# SolderingStation_Control_-_Using_Mux_for.net
KiCad netlist of a schematic drawn in Altium Designer
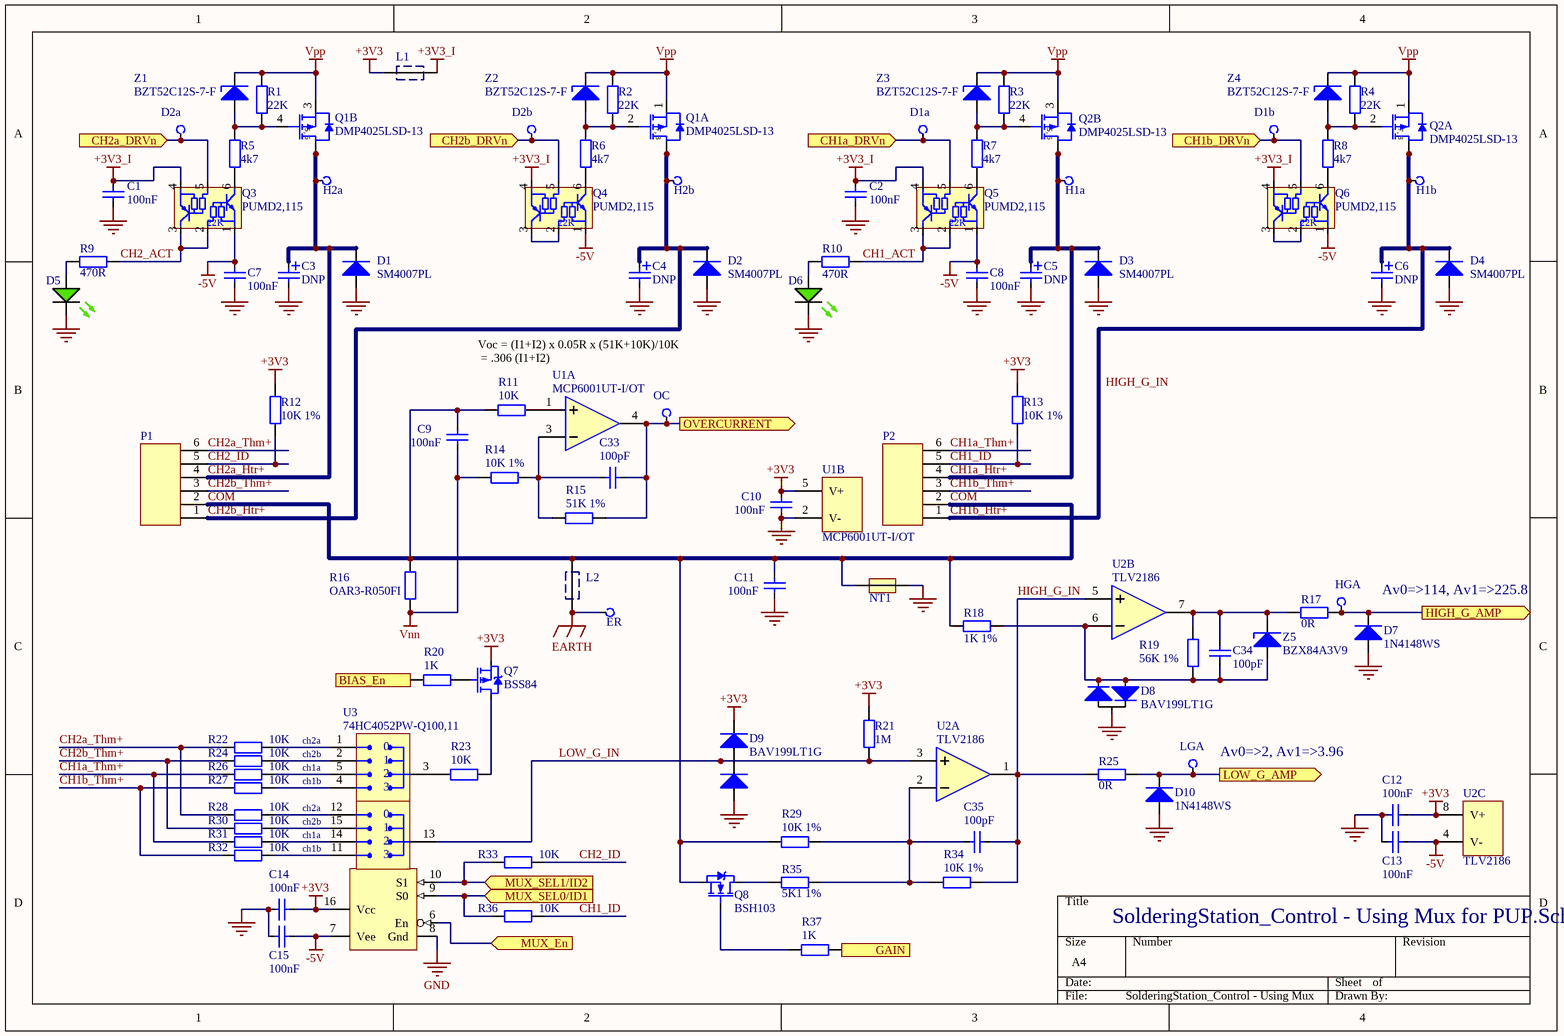
[diagram p0: SolderingStation_Control - Using Mux for PUP.SchDoc]

(export (version "E")
  (design (tool "Eeschema 10.0.6"))
  (components
    (comp (ref "C1")
      (value "100nF")
      (footprint "CCNP1608-0603")
      (description "Capacitor non-polar SMT 0603")
      (fields
        (field (name "MANUFACTURER") "Generic Components")
        (field (name "PUBLISHER") "Altium Hobart Technology Centre")
      )
      (libsource (lib "MyLibrary") (part "Cap_CCNP_0603"))
    )
    (comp (ref "C2")
      (value "100nF")
      (footprint "CCNP1608-0603")
      (description "Capacitor non-polar SMT 0603")
      (fields
        (field (name "MANUFACTURER") "Generic Components")
        (field (name "PUBLISHER") "Altium Hobart Technology Centre")
      )
      (libsource (lib "MyLibrary") (part "Cap_CCNP_0603"))
    )
    (comp (ref "C3")
      (value "DNP")
      (footprint "CC2012-0805")
      (description "Capacitor SMT 0805")
      (fields
        (field (name "MANUFACTURER") "Generic Components")
        (field (name "PUBLISHER") "Altium Hobart Technology Centre")
      )
      (libsource (lib "MyLibrary") (part "Cap_CC_0805"))
    )
    (comp (ref "C4")
      (value "DNP")
      (footprint "CC2012-0805")
      (description "Capacitor SMT 0805")
      (fields
        (field (name "MANUFACTURER") "Generic Components")
        (field (name "PUBLISHER") "Altium Hobart Technology Centre")
      )
      (libsource (lib "MyLibrary") (part "Cap_CC_0805"))
    )
    (comp (ref "C5")
      (value "DNP")
      (footprint "CC2012-0805")
      (description "Capacitor SMT 0805")
      (fields
        (field (name "MANUFACTURER") "Generic Components")
        (field (name "PUBLISHER") "Altium Hobart Technology Centre")
      )
      (libsource (lib "MyLibrary") (part "Cap_CC_0805"))
    )
    (comp (ref "C6")
      (value "DNP")
      (footprint "CC2012-0805")
      (description "Capacitor SMT 0805")
      (fields
        (field (name "MANUFACTURER") "Generic Components")
        (field (name "PUBLISHER") "Altium Hobart Technology Centre")
      )
      (libsource (lib "MyLibrary") (part "Cap_CC_0805"))
    )
    (comp (ref "C7")
      (value "100nF")
      (footprint "CCNP1608-0603")
      (description "Capacitor non-polar SMT 0603")
      (fields
        (field (name "MANUFACTURER") "Generic Components")
        (field (name "PUBLISHER") "Altium Hobart Technology Centre")
      )
      (libsource (lib "MyLibrary") (part "Cap_CCNP_0603"))
    )
    (comp (ref "C8")
      (value "100nF")
      (footprint "CCNP1608-0603")
      (description "Capacitor non-polar SMT 0603")
      (fields
        (field (name "MANUFACTURER") "Generic Components")
        (field (name "PUBLISHER") "Altium Hobart Technology Centre")
      )
      (libsource (lib "MyLibrary") (part "Cap_CCNP_0603"))
    )
    (comp (ref "C9")
      (value "100nF")
      (footprint "CCNP1608-0603")
      (description "Capacitor non-polar SMT 0603")
      (fields
        (field (name "MANUFACTURER") "Generic Components")
        (field (name "PUBLISHER") "Altium Hobart Technology Centre")
      )
      (libsource (lib "MyLibrary") (part "Cap_CCNP_0603"))
    )
    (comp (ref "C10")
      (value "100nF")
      (footprint "CCNP1608-0603")
      (description "Capacitor non-polar SMT 0603")
      (fields
        (field (name "MANUFACTURER") "Generic Components")
        (field (name "PUBLISHER") "Altium Hobart Technology Centre")
      )
      (libsource (lib "MyLibrary") (part "Cap_CCNP_0603"))
    )
    (comp (ref "C11")
      (value "100nF")
      (footprint "CCNP1608-0603")
      (description "Capacitor non-polar SMT 0603")
      (fields
        (field (name "MANUFACTURER") "Generic Components")
        (field (name "PUBLISHER") "Altium Hobart Technology Centre")
      )
      (libsource (lib "MyLibrary") (part "Cap_CCNP_0603"))
    )
    (comp (ref "C12")
      (value "100nF")
      (footprint "CCNP1608-0603")
      (description "Capacitor non-polar SMT 0603")
      (fields
        (field (name "MANUFACTURER") "Generic Components")
        (field (name "PUBLISHER") "Altium Hobart Technology Centre")
      )
      (libsource (lib "MyLibrary") (part "Cap_CCNP_0603"))
    )
    (comp (ref "C13")
      (value "100nF")
      (footprint "CCNP1608-0603")
      (description "Capacitor non-polar SMT 0603")
      (fields
        (field (name "MANUFACTURER") "Generic Components")
        (field (name "PUBLISHER") "Altium Hobart Technology Centre")
      )
      (libsource (lib "MyLibrary") (part "Cap_CCNP_0603"))
    )
    (comp (ref "C14")
      (value "100nF")
      (footprint "CCNP1608-0603")
      (description "Capacitor non-polar SMT 0603")
      (fields
        (field (name "MANUFACTURER") "Generic Components")
        (field (name "PUBLISHER") "Altium Hobart Technology Centre")
      )
      (libsource (lib "MyLibrary") (part "Cap_CCNP_0603"))
    )
    (comp (ref "C15")
      (value "100nF")
      (footprint "CCNP1608-0603")
      (description "Capacitor non-polar SMT 0603")
      (fields
        (field (name "MANUFACTURER") "Generic Components")
        (field (name "PUBLISHER") "Altium Hobart Technology Centre")
      )
      (libsource (lib "MyLibrary") (part "Cap_CCNP_0603"))
    )
    (comp (ref "C33")
      (value "100pF")
      (footprint "CCNP1608-0603")
      (description "Capacitor non-polar SMT 0603")
      (fields
        (field (name "MANUFACTURER") "Generic Components")
        (field (name "PUBLISHER") "Altium Hobart Technology Centre")
      )
      (libsource (lib "MyLibrary") (part "Cap_CCNP_0603"))
    )
    (comp (ref "C34")
      (value "100pF")
      (footprint "CCNP1608-0603")
      (description "Capacitor non-polar SMT 0603")
      (fields
        (field (name "MANUFACTURER") "Generic Components")
        (field (name "PUBLISHER") "Altium Hobart Technology Centre")
      )
      (libsource (lib "MyLibrary") (part "Cap_CCNP_0603"))
    )
    (comp (ref "C35")
      (value "100pF")
      (footprint "CCNP1608-0603")
      (description "Capacitor non-polar SMT 0603")
      (fields
        (field (name "MANUFACTURER") "Generic Components")
        (field (name "PUBLISHER") "Altium Hobart Technology Centre")
      )
      (libsource (lib "MyLibrary") (part "Cap_CCNP_0603"))
    )
    (comp (ref "D1")
      (value "SM4007PL")
      (footprint "SOD-123FL")
      (description "Diodes - General Purpose, 1kV 1A 1.1V 1A SOD-123FL")
      (libsource (lib "MyLibrary") (part "SM4007PL"))
    )
    (comp (ref "D1a")
      (value "Drive1")
      (footprint "PCBPIN - 0.7mm")
      (description "Test Point")
      (libsource (lib "MyLibrary") (part "TP"))
    )
    (comp (ref "D1b")
      (value "Drive2")
      (footprint "PCBPIN - 0.7mm")
      (description "Test Point")
      (libsource (lib "MyLibrary") (part "TP"))
    )
    (comp (ref "D2")
      (value "SM4007PL")
      (footprint "SOD-123FL")
      (description "Diodes - General Purpose, 1kV 1A 1.1V 1A SOD-123FL")
      (libsource (lib "MyLibrary") (part "SM4007PL"))
    )
    (comp (ref "D2a")
      (value "Drive2")
      (footprint "PCBPIN - 0.7mm")
      (description "Test Point")
      (libsource (lib "MyLibrary") (part "TP"))
    )
    (comp (ref "D2b")
      (value "Drive2")
      (footprint "PCBPIN - 0.7mm")
      (description "Test Point")
      (libsource (lib "MyLibrary") (part "TP"))
    )
    (comp (ref "D3")
      (value "SM4007PL")
      (footprint "SOD-123FL")
      (description "Diodes - General Purpose, 1kV 1A 1.1V 1A SOD-123FL")
      (libsource (lib "MyLibrary") (part "SM4007PL"))
    )
    (comp (ref "D4")
      (value "SM4007PL")
      (footprint "SOD-123FL")
      (description "Diodes - General Purpose, 1kV 1A 1.1V 1A SOD-123FL")
      (libsource (lib "MyLibrary") (part "SM4007PL"))
    )
    (comp (ref "D5")
      (value "LED")
      (footprint "LED3MM-GREEN - 10mm Proud")
      (description "3mm Green LED")
      (fields (field (name "MANUFACTURER") "Generic Components") (field (name "PUBLISHER") "Altium Limited"))
      (libsource (lib "MySchLib") (part "LED_3MM_GREEN"))
    )
    (comp (ref "D6")
      (value "LED")
      (footprint "LED3MM-GREEN - 10mm Proud")
      (description "3mm Green LED")
      (fields (field (name "MANUFACTURER") "Generic Components") (field (name "PUBLISHER") "Altium Limited"))
      (libsource (lib "MySchLib") (part "LED_3MM_GREEN"))
    )
    (comp (ref "D7")
      (value "1N4148WS")
      (footprint "SOD-323")
      (description "Switching Diode 100V 150mA 1.25V@150mA 4ns SOD-323")
      (libsource (lib "MyLibrary") (part "1N4148WS"))
    )
    (comp (ref "D8")
      (value "BAV199LT1G")
      (footprint "SOT23_M")
      (description "Dual Series low-leakage switching diodes, 3-Pin SOT-23")
      (libsource (lib "MyLibrary") (part "BAV199LT1G"))
    )
    (comp (ref "D9")
      (value "BAV199LT1G")
      (footprint "SOT23_M")
      (description "Dual Series low-leakage switching diodes, 3-Pin SOT-23")
      (libsource (lib "MySchLib") (part "BAV199LT1G"))
    )
    (comp (ref "D10")
      (value "1N4148WS")
      (footprint "SOD-323")
      (description "Switching Diode 100V 150mA 1.25V@150mA 4ns SOD-323")
      (libsource (lib "MyLibrary") (part "1N4148WS"))
    )
    (comp (ref "ER")
      (value "Gnd")
      (footprint "PCBPIN - 1mm")
      (description "Test Point")
      (libsource (lib "") (part "TP_1"))
    )
    (comp (ref "H1a")
      (value "Heater1")
      (footprint "PCBPIN - 0.7mm")
      (description "Test Point")
      (libsource (lib "") (part "TP_1"))
    )
    (comp (ref "H1b")
      (value "Heater2")
      (footprint "PCBPIN - 0.7mm")
      (description "Test Point")
      (libsource (lib "") (part "TP_1"))
    )
    (comp (ref "H2a")
      (value "Heater2")
      (footprint "PCBPIN - 0.7mm")
      (description "Test Point")
      (libsource (lib "") (part "TP_1"))
    )
    (comp (ref "H2b")
      (value "Heater2")
      (footprint "PCBPIN - 0.7mm")
      (description "Test Point")
      (libsource (lib "") (part "TP_1"))
    )
    (comp (ref "HGA")
      (value "TC1")
      (footprint "PCBPIN - 0.7mm")
      (description "Test Point")
      (libsource (lib "MyLibrary") (part "TP"))
    )
    (comp (ref "L1")
      (value "Ferrite Bead")
      (footprint "FB2012-0805")
      (description "Ferrite Bead SMT 0805, TDK MPZ2012S102AT, 0.15OHM, 1.5A")
      (libsource (lib "MySchLib") (part "Ferrite Bead 0805"))
    )
    (comp (ref "L2")
      (value "Ferrite Bead")
      (footprint "FB2012-0805")
      (description "Ferrite Bead SMT 0805, TDK MPZ2012S102AT, 0.15OHM, 1.5A")
      (libsource (lib "MySchLib") (part "Ferrite Bead 0805"))
    )
    (comp (ref "LGA")
      (value "NTC1")
      (footprint "PCBPIN - 0.7mm")
      (description "Test Point")
      (libsource (lib "MyLibrary") (part "TP"))
    )
    (comp (ref "NT1")
      (value "NetTieVia")
      (footprint "NetTieVia")
      (libsource (lib "MyLibrary") (part "NetTieVia"))
    )
    (comp (ref "OC")
      (value "Overcurrent")
      (footprint "PCBPIN - 0.7mm")
      (description "Test Point")
      (libsource (lib "MyLibrary") (part "TP"))
    )
    (comp (ref "P1")
      (value "MOLEX-43045-0612")
      (footprint "MOLEX-43045-0612")
      (description "Wire-To-Board Connector, With Polarizing Peg, 3 mm, 6 Contacts, Header, Micro-Fit 3.0 43045 Series")
      (libsource (lib "MySchLib") (part "MOLEX-43045-0612"))
    )
    (comp (ref "P2")
      (value "MOLEX-43045-0612")
      (footprint "MOLEX-43045-0612")
      (description "Wire-To-Board Connector, With Polarizing Peg, 3 mm, 6 Contacts, Header, Micro-Fit 3.0 43045 Series")
      (libsource (lib "MySchLib") (part "MOLEX-43045-0612"))
    )
    (comp (ref "Q1")
      (value "DMP4025LSD-13")
      (footprint "SO-8_M")
      (description "P-Channel dual MOSFET, 40 V, 7.6 A, 0.018 ohm, SOIC, Surface Mount")
      (libsource (lib "MyLibrary") (part "DMP4025LSD-13"))
    )
    (comp (ref "Q2")
      (value "DMP4025LSD-13")
      (footprint "SO-8_M")
      (description "P-Channel dual MOSFET, 40 V, 7.6 A, 0.018 ohm, SOIC, Surface Mount")
      (libsource (lib "MyLibrary") (part "DMP4025LSD-13"))
    )
    (comp (ref "Q3")
      (value "PUMD2,115")
      (footprint "SOT363-6M")
      (description "Pre-Biased NPN and PNP pair, 50 V, 100 mA, 22 kohm, 22 kohm")
      (libsource (lib "MyLibrary") (part "PUMD2,115"))
    )
    (comp (ref "Q4")
      (value "PUMD2,115")
      (footprint "SOT363-6M")
      (description "Pre-Biased NPN and PNP pair, 50 V, 100 mA, 22 kohm, 22 kohm")
      (libsource (lib "MyLibrary") (part "PUMD2,115"))
    )
    (comp (ref "Q5")
      (value "PUMD2,115")
      (footprint "SOT363-6M")
      (description "Pre-Biased NPN and PNP pair, 50 V, 100 mA, 22 kohm, 22 kohm")
      (libsource (lib "MyLibrary") (part "PUMD2,115"))
    )
    (comp (ref "Q6")
      (value "PUMD2,115")
      (footprint "SOT363-6M")
      (description "Pre-Biased NPN and PNP pair, 50 V, 100 mA, 22 kohm, 22 kohm")
      (libsource (lib "MyLibrary") (part "PUMD2,115"))
    )
    (comp (ref "Q7")
      (value "BSS84")
      (footprint "SOT23_M")
      (description "P-Channel Enhancement Mode FET -0.13 A, -50 V,  RDS(ON) = 10R at VGS = -5 V")
      (libsource (lib "MySchLib") (part "BSS84"))
    )
    (comp (ref "Q8")
      (value "BSH103")
      (footprint "SOT23_N")
      (description "N-channel enhancement mode FET, , 30 V, 850 mA, 0.4 ohm, SOT23")
      (libsource (lib "MyLibrary") (part "BSH103"))
    )
    (comp (ref "R1")
      (value "22K")
      (footprint "CR1608-0603_N")
      (description "Resistor SMT 0603")
      (fields
        (field (name "MANUFACTURER") "Generic Components")
        (field (name "PUBLISHER") "Altium Hobart Technology Centre")
      )
      (libsource (lib "MyLibrary") (part "Res_CR0603"))
    )
    (comp (ref "R2")
      (value "22K")
      (footprint "CR1608-0603_N")
      (description "Resistor SMT 0603")
      (fields
        (field (name "MANUFACTURER") "Generic Components")
        (field (name "PUBLISHER") "Altium Hobart Technology Centre")
      )
      (libsource (lib "MyLibrary") (part "Res_CR0603"))
    )
    (comp (ref "R3")
      (value "22K")
      (footprint "CR1608-0603_N")
      (description "Resistor SMT 0603")
      (fields
        (field (name "MANUFACTURER") "Generic Components")
        (field (name "PUBLISHER") "Altium Hobart Technology Centre")
      )
      (libsource (lib "MyLibrary") (part "Res_CR0603"))
    )
    (comp (ref "R4")
      (value "22K")
      (footprint "CR1608-0603_N")
      (description "Resistor SMT 0603")
      (fields
        (field (name "MANUFACTURER") "Generic Components")
        (field (name "PUBLISHER") "Altium Hobart Technology Centre")
      )
      (libsource (lib "MyLibrary") (part "Res_CR0603"))
    )
    (comp (ref "R5")
      (value "4k7")
      (footprint "CR1608-0603_N")
      (description "Resistor SMT 0603")
      (fields
        (field (name "MANUFACTURER") "Generic Components")
        (field (name "PUBLISHER") "Altium Hobart Technology Centre")
      )
      (libsource (lib "MyLibrary") (part "Res_CR0603"))
    )
    (comp (ref "R6")
      (value "4k7")
      (footprint "CR1608-0603_N")
      (description "Resistor SMT 0603")
      (fields
        (field (name "MANUFACTURER") "Generic Components")
        (field (name "PUBLISHER") "Altium Hobart Technology Centre")
      )
      (libsource (lib "MyLibrary") (part "Res_CR0603"))
    )
    (comp (ref "R7")
      (value "4k7")
      (footprint "CR1608-0603_N")
      (description "Resistor SMT 0603")
      (fields
        (field (name "MANUFACTURER") "Generic Components")
        (field (name "PUBLISHER") "Altium Hobart Technology Centre")
      )
      (libsource (lib "MyLibrary") (part "Res_CR0603"))
    )
    (comp (ref "R8")
      (value "4k7")
      (footprint "CR1608-0603_N")
      (description "Resistor SMT 0603")
      (fields
        (field (name "MANUFACTURER") "Generic Components")
        (field (name "PUBLISHER") "Altium Hobart Technology Centre")
      )
      (libsource (lib "MyLibrary") (part "Res_CR0603"))
    )
    (comp (ref "R9")
      (value "470R")
      (footprint "CR1608-0603_N")
      (description "Resistor SMT 0603")
      (fields
        (field (name "MANUFACTURER") "Generic Components")
        (field (name "PUBLISHER") "Altium Hobart Technology Centre")
      )
      (libsource (lib "") (part "Res_CR0603_3"))
    )
    (comp (ref "R10")
      (value "470R")
      (footprint "CR1608-0603_N")
      (description "Resistor SMT 0603")
      (fields
        (field (name "MANUFACTURER") "Generic Components")
        (field (name "PUBLISHER") "Altium Hobart Technology Centre")
      )
      (libsource (lib "") (part "Res_CR0603_3"))
    )
    (comp (ref "R11")
      (value "10K")
      (footprint "CR1608-0603_N")
      (description "Resistor SMT 0603")
      (fields
        (field (name "MANUFACTURER") "Generic Components")
        (field (name "PUBLISHER") "Altium Hobart Technology Centre")
      )
      (libsource (lib "") (part "Res_CR0603_2"))
    )
    (comp (ref "R12")
      (value "10K 1%")
      (footprint "CR1608-0603_N")
      (description "Resistor SMT 0603")
      (fields
        (field (name "MANUFACTURER") "Generic Components")
        (field (name "PUBLISHER") "Altium Hobart Technology Centre")
      )
      (libsource (lib "MyLibrary") (part "Res_CR0603"))
    )
    (comp (ref "R13")
      (value "10K 1%")
      (footprint "CR1608-0603_N")
      (description "Resistor SMT 0603")
      (fields
        (field (name "MANUFACTURER") "Generic Components")
        (field (name "PUBLISHER") "Altium Hobart Technology Centre")
      )
      (libsource (lib "MyLibrary") (part "Res_CR0603"))
    )
    (comp (ref "R14")
      (value "10K 1%")
      (footprint "CR1608-0603_N")
      (description "Resistor SMT 0603")
      (fields
        (field (name "MANUFACTURER") "Generic Components")
        (field (name "PUBLISHER") "Altium Hobart Technology Centre")
      )
      (libsource (lib "") (part "Res_CR0603_2"))
    )
    (comp (ref "R15")
      (value "51K 1%")
      (footprint "CR1608-0603_N")
      (description "Resistor SMT 0603")
      (fields
        (field (name "MANUFACTURER") "Generic Components")
        (field (name "PUBLISHER") "Altium Hobart Technology Centre")
      )
      (libsource (lib "") (part "Res_CR0603_3"))
    )
    (comp (ref "R16")
      (value "OAR3-R050FI")
      (footprint "OAR3-R050FI")
      (description "Current Sense Resistor, 0.05 ohm, OAR Series, 3 W, Metal Strip, Radial Leaded, 1%")
      (libsource (lib "MySchLib") (part "OAR3-R050FI"))
    )
    (comp (ref "R17")
      (value "0R")
      (footprint "CR1608-0603_N")
      (description "Resistor SMT 0603")
      (fields
        (field (name "MANUFACTURER") "Generic Components")
        (field (name "PUBLISHER") "Altium Hobart Technology Centre")
      )
      (libsource (lib "") (part "Res_CR0603_1"))
    )
    (comp (ref "R18")
      (value "1K 1%")
      (footprint "CR1608-0603_N")
      (description "Resistor SMT 0603")
      (fields
        (field (name "MANUFACTURER") "Generic Components")
        (field (name "PUBLISHER") "Altium Hobart Technology Centre")
      )
      (libsource (lib "") (part "Res_CR0603_2"))
    )
    (comp (ref "R19")
      (value "56K 1%")
      (footprint "CR1608-0603_N")
      (description "Resistor SMT 0603")
      (fields
        (field (name "MANUFACTURER") "Generic Components")
        (field (name "PUBLISHER") "Altium Hobart Technology Centre")
      )
      (libsource (lib "MyLibrary") (part "Res_CR0603"))
    )
    (comp (ref "R20")
      (value "1K")
      (footprint "CR1608-0603_N")
      (description "Resistor SMT 0603")
      (fields
        (field (name "MANUFACTURER") "Generic Components")
        (field (name "PUBLISHER") "Altium Hobart Technology Centre")
      )
      (libsource (lib "MyLibrary") (part "Res_CR0603"))
    )
    (comp (ref "R21")
      (value "1M")
      (footprint "CR1608-0603_N")
      (description "Resistor SMT 0603")
      (fields
        (field (name "MANUFACTURER") "Generic Components")
        (field (name "PUBLISHER") "Altium Hobart Technology Centre")
      )
      (libsource (lib "") (part "Res_CR0603_3"))
    )
    (comp (ref "R22")
      (value "10K")
      (footprint "CR1608-0603_N")
      (description "Resistor SMT 0603")
      (fields
        (field (name "MANUFACTURER") "Generic Components")
        (field (name "PUBLISHER") "Altium Hobart Technology Centre")
      )
      (libsource (lib "") (part "Res_CR0603_1"))
    )
    (comp (ref "R23")
      (value "10K")
      (footprint "CR1608-0603_N")
      (description "Resistor SMT 0603")
      (fields
        (field (name "MANUFACTURER") "Generic Components")
        (field (name "PUBLISHER") "Altium Hobart Technology Centre")
      )
      (libsource (lib "") (part "Res_CR0603_1"))
    )
    (comp (ref "R24")
      (value "10K")
      (footprint "CR1608-0603_N")
      (description "Resistor SMT 0603")
      (fields
        (field (name "MANUFACTURER") "Generic Components")
        (field (name "PUBLISHER") "Altium Hobart Technology Centre")
      )
      (libsource (lib "") (part "Res_CR0603_1"))
    )
    (comp (ref "R25")
      (value "0R")
      (footprint "CR1608-0603_N")
      (description "Resistor SMT 0603")
      (fields
        (field (name "MANUFACTURER") "Generic Components")
        (field (name "PUBLISHER") "Altium Hobart Technology Centre")
      )
      (libsource (lib "") (part "Res_CR0603_1"))
    )
    (comp (ref "R26")
      (value "10K")
      (footprint "CR1608-0603_N")
      (description "Resistor SMT 0603")
      (fields
        (field (name "MANUFACTURER") "Generic Components")
        (field (name "PUBLISHER") "Altium Hobart Technology Centre")
      )
      (libsource (lib "") (part "Res_CR0603_1"))
    )
    (comp (ref "R27")
      (value "10K")
      (footprint "CR1608-0603_N")
      (description "Resistor SMT 0603")
      (fields
        (field (name "MANUFACTURER") "Generic Components")
        (field (name "PUBLISHER") "Altium Hobart Technology Centre")
      )
      (libsource (lib "") (part "Res_CR0603_1"))
    )
    (comp (ref "R28")
      (value "10K")
      (footprint "CR1608-0603_N")
      (description "Resistor SMT 0603")
      (fields
        (field (name "MANUFACTURER") "Generic Components")
        (field (name "PUBLISHER") "Altium Hobart Technology Centre")
      )
      (libsource (lib "") (part "Res_CR0603_1"))
    )
    (comp (ref "R29")
      (value "10K 1%")
      (footprint "CR1608-0603_N")
      (description "Resistor SMT 0603")
      (fields
        (field (name "MANUFACTURER") "Generic Components")
        (field (name "PUBLISHER") "Altium Hobart Technology Centre")
      )
      (libsource (lib "") (part "Res_CR0603_3"))
    )
    (comp (ref "R30")
      (value "10K")
      (footprint "CR1608-0603_N")
      (description "Resistor SMT 0603")
      (fields
        (field (name "MANUFACTURER") "Generic Components")
        (field (name "PUBLISHER") "Altium Hobart Technology Centre")
      )
      (libsource (lib "") (part "Res_CR0603_1"))
    )
    (comp (ref "R31")
      (value "10K")
      (footprint "CR1608-0603_N")
      (description "Resistor SMT 0603")
      (fields
        (field (name "MANUFACTURER") "Generic Components")
        (field (name "PUBLISHER") "Altium Hobart Technology Centre")
      )
      (libsource (lib "") (part "Res_CR0603_1"))
    )
    (comp (ref "R32")
      (value "10K")
      (footprint "CR1608-0603_N")
      (description "Resistor SMT 0603")
      (fields
        (field (name "MANUFACTURER") "Generic Components")
        (field (name "PUBLISHER") "Altium Hobart Technology Centre")
      )
      (libsource (lib "") (part "Res_CR0603_1"))
    )
    (comp (ref "R33")
      (value "10K")
      (footprint "CR1608-0603_N")
      (description "Resistor SMT 0603")
      (fields
        (field (name "MANUFACTURER") "Generic Components")
        (field (name "PUBLISHER") "Altium Hobart Technology Centre")
      )
      (libsource (lib "") (part "Res_CR0603_1"))
    )
    (comp (ref "R34")
      (value "10K 1%")
      (footprint "CR1608-0603_N")
      (description "Resistor SMT 0603")
      (fields
        (field (name "MANUFACTURER") "Generic Components")
        (field (name "PUBLISHER") "Altium Hobart Technology Centre")
      )
      (libsource (lib "") (part "Res_CR0603_3"))
    )
    (comp (ref "R35")
      (value "5K1 1%")
      (footprint "CR1608-0603_N")
      (description "Resistor SMT 0603")
      (fields
        (field (name "MANUFACTURER") "Generic Components")
        (field (name "PUBLISHER") "Altium Hobart Technology Centre")
      )
      (libsource (lib "") (part "Res_CR0603_1"))
    )
    (comp (ref "R36")
      (value "10K")
      (footprint "CR1608-0603_N")
      (description "Resistor SMT 0603")
      (fields
        (field (name "MANUFACTURER") "Generic Components")
        (field (name "PUBLISHER") "Altium Hobart Technology Centre")
      )
      (libsource (lib "") (part "Res_CR0603_1"))
    )
    (comp (ref "R37")
      (value "1K")
      (footprint "CR1608-0603_N")
      (description "Resistor SMT 0603")
      (fields
        (field (name "MANUFACTURER") "Generic Components")
        (field (name "PUBLISHER") "Altium Hobart Technology Centre")
      )
      (libsource (lib "MyLibrary") (part "Res_CR0603"))
    )
    (comp (ref "U1")
      (value "MCP6001UT-I/OT")
      (footprint "SOT23-5_M")
      (description "Op-Amp, Single supply R-R in/out")
      (libsource (lib "MySchLib") (part "MCP6001UT-I/OT"))
    )
    (comp (ref "U2")
      (value "TLV2186")
      (footprint "SOIC127P600-8M")
      (description "Dual Precision,Rail-to-Rail Input and Output, 4.5-24V, Zero-Drift OperationalAmplifier")
      (libsource (lib "MySchLib") (part "TLV2186"))
    )
    (comp (ref "U3")
      (value "74HC4052PW-Q100,11")
      (footprint "TSSOP16_M")
      (description "Analog Multiplexer / Demultiplexer, 4:1, 2 Circuits, 225 ohm, 2V to 10V, TSSOP-16")
      (libsource (lib "MySchLib") (part "74HC4052PW-Q100,11"))
    )
    (comp (ref "Z1")
      (value "BZT52C12S-7-F")
      (footprint "SOD-323")
      (description "Surface Mount Zener Diode, 12-13 V, -65 to 150 degC, SOD-123")
      (libsource (lib "MySchLib") (part "BZT52C12S-7-F"))
    )
    (comp (ref "Z2")
      (value "BZT52C12S-7-F")
      (footprint "SOD-323")
      (description "Surface Mount Zener Diode, 12-13 V, -65 to 150 degC, SOD-123")
      (libsource (lib "MySchLib") (part "BZT52C12S-7-F"))
    )
    (comp (ref "Z3")
      (value "BZT52C12S-7-F")
      (footprint "SOD-323")
      (description "Surface Mount Zener Diode, 12-13 V, -65 to 150 degC, SOD-123")
      (libsource (lib "MySchLib") (part "BZT52C12S-7-F"))
    )
    (comp (ref "Z4")
      (value "BZT52C12S-7-F")
      (footprint "SOD-323")
      (description "Surface Mount Zener Diode, 12-13 V, -65 to 150 degC, SOD-123")
      (libsource (lib "MySchLib") (part "BZT52C12S-7-F"))
    )
    (comp (ref "Z5")
      (value "BZX84A3V9")
      (footprint "SOT23_M")
      (description "Zener Diode, 3.9V, 250mW, SOT-23, 1%, 150C")
      (fields
        (field (name "MANUFACTURER") "Generic Components")
        (field (name "PUBLISHER") "Altium Hobart Technology Centre")
      )
      (libsource (lib "MyLibrary") (part "BZX84A3V9"))
    )
  )
  (nets
    (net (code "1") (name "+3V3") (class "Default")
      (node (ref "C10") (pin "1") (pinfunction "1_1") (pintype "passive"))
      (node (ref "C12") (pin "1") (pinfunction "1_1") (pintype "passive"))
      (node (ref "C14") (pin "1") (pinfunction "1_1") (pintype "passive"))
      (node (ref "D9") (pin "2") (pinfunction "A2_2") (pintype "passive"))
      (node (ref "L1") (pin "1") (pinfunction "1_1") (pintype "passive"))
      (node (ref "Q7") (pin "2") (pinfunction "S_2") (pintype "passive"))
      (node (ref "R12") (pin "2") (pinfunction "2_2") (pintype "passive"))
      (node (ref "R13") (pin "2") (pinfunction "2_2") (pintype "passive"))
      (node (ref "R21") (pin "2") (pinfunction "2_2") (pintype "passive"))
      (node (ref "U1") (pin "5") (pinfunction "V+_5") (pintype "power_in"))
      (node (ref "U2") (pin "8") (pinfunction "V+_8") (pintype "power_in"))
      (node (ref "U3") (pin "16") (pinfunction "Vcc_16") (pintype "power_in"))
    )
    (net (code "2") (name "+3V3_I") (class "Default")
      (node (ref "C1") (pin "1") (pinfunction "1_1") (pintype "passive"))
      (node (ref "C2") (pin "1") (pinfunction "1_1") (pintype "passive"))
      (node (ref "L1") (pin "2") (pinfunction "2_2") (pintype "passive"))
      (node (ref "Q3") (pin "4") (pinfunction "E2_4") (pintype "passive"))
      (node (ref "Q4") (pin "4") (pinfunction "E2_4") (pintype "passive"))
      (node (ref "Q5") (pin "4") (pinfunction "E2_4") (pintype "passive"))
      (node (ref "Q6") (pin "4") (pinfunction "E2_4") (pintype "passive"))
    )
    (net (code "3") (name "-5V") (class "Default")
      (node (ref "C13") (pin "1") (pinfunction "1_1") (pintype "passive"))
      (node (ref "C15") (pin "1") (pinfunction "1_1") (pintype "passive"))
      (node (ref "C7") (pin "1") (pinfunction "1_1") (pintype "passive"))
      (node (ref "C8") (pin "1") (pinfunction "1_1") (pintype "passive"))
      (node (ref "Q3") (pin "1") (pinfunction "E1_1") (pintype "passive"))
      (node (ref "Q4") (pin "1") (pinfunction "E1_1") (pintype "passive"))
      (node (ref "Q5") (pin "1") (pinfunction "E1_1") (pintype "passive"))
      (node (ref "Q6") (pin "1") (pinfunction "E1_1") (pintype "passive"))
      (node (ref "U2") (pin "4") (pinfunction "V-_4") (pintype "power_in"))
      (node (ref "U3") (pin "7") (pinfunction "Vee_7") (pintype "power_in"))
    )
    (net (code "4") (name "/BIAS_En") (class "Default")
      (node (ref "R20") (pin "1") (pinfunction "1_1") (pintype "passive"))
    )
    (net (code "5") (name "/CH1_ACT") (class "Default")
      (node (ref "Q5") (pin "2") (pinfunction "B1_2") (pintype "passive"))
      (node (ref "Q5") (pin "3") (pinfunction "C2_3") (pintype "passive"))
      (node (ref "R10") (pin "2") (pinfunction "2_2") (pintype "passive"))
    )
    (net (code "6") (name "/CH1_ID") (class "Default")
      (node (ref "P2") (pin "5") (pinfunction "5_5") (pintype "passive"))
      (node (ref "R13") (pin "1") (pinfunction "1_1") (pintype "passive"))
      (node (ref "R36") (pin "1") (pinfunction "1_1") (pintype "passive"))
    )
    (net (code "7") (name "/CH1a_DRVn") (class "Default")
      (node (ref "D1a") (pin "1") (pinfunction "TP_1") (pintype "passive"))
      (node (ref "Q5") (pin "5") (pinfunction "B2_5") (pintype "passive"))
    )
    (net (code "8") (name "/CH1a_Htr+") (class "Default")
      (node (ref "C5") (pin "1") (pinfunction "1_1") (pintype "passive"))
      (node (ref "D3") (pin "K") (pinfunction "K_K") (pintype "passive"))
      (node (ref "H1a") (pin "1") (pinfunction "TP_1") (pintype "passive"))
      (node (ref "P2") (pin "4") (pinfunction "4_4") (pintype "passive"))
      (node (ref "Q2") (pin "5") (pinfunction "D2_5") (pintype "passive"))
      (node (ref "Q2") (pin "6") (pinfunction "D2_6") (pintype "passive"))
    )
    (net (code "9") (name "/CH1a_Thm+") (class "Default")
      (node (ref "P2") (pin "6") (pinfunction "6_6") (pintype "passive"))
      (node (ref "R26") (pin "2") (pinfunction "2_2") (pintype "passive"))
      (node (ref "R31") (pin "2") (pinfunction "2_2") (pintype "passive"))
    )
    (net (code "10") (name "/CH1b_DRVn") (class "Default")
      (node (ref "D1b") (pin "1") (pinfunction "TP_1") (pintype "passive"))
      (node (ref "Q6") (pin "5") (pinfunction "B2_5") (pintype "passive"))
    )
    (net (code "11") (name "/CH1b_Htr+") (class "Default")
      (node (ref "C6") (pin "1") (pinfunction "1_1") (pintype "passive"))
      (node (ref "D4") (pin "K") (pinfunction "K_K") (pintype "passive"))
      (node (ref "H1b") (pin "1") (pinfunction "TP_1") (pintype "passive"))
      (node (ref "P2") (pin "1") (pinfunction "1_1") (pintype "passive"))
      (node (ref "Q2") (pin "7") (pinfunction "D1_7") (pintype "passive"))
      (node (ref "Q2") (pin "8") (pinfunction "D1_8") (pintype "passive"))
    )
    (net (code "12") (name "/CH1b_Thm+") (class "Default")
      (node (ref "P2") (pin "3") (pinfunction "3_3") (pintype "passive"))
      (node (ref "R27") (pin "2") (pinfunction "2_2") (pintype "passive"))
      (node (ref "R32") (pin "2") (pinfunction "2_2") (pintype "passive"))
    )
    (net (code "13") (name "/CH2_ACT") (class "Default")
      (node (ref "Q3") (pin "2") (pinfunction "B1_2") (pintype "passive"))
      (node (ref "Q3") (pin "3") (pinfunction "C2_3") (pintype "passive"))
      (node (ref "R9") (pin "2") (pinfunction "2_2") (pintype "passive"))
    )
    (net (code "14") (name "/CH2_ID") (class "Default")
      (node (ref "P1") (pin "5") (pinfunction "5_5") (pintype "passive"))
      (node (ref "R12") (pin "1") (pinfunction "1_1") (pintype "passive"))
      (node (ref "R33") (pin "1") (pinfunction "1_1") (pintype "passive"))
    )
    (net (code "15") (name "/CH2a_DRVn") (class "Default")
      (node (ref "D2a") (pin "1") (pinfunction "TP_1") (pintype "passive"))
      (node (ref "Q3") (pin "5") (pinfunction "B2_5") (pintype "passive"))
    )
    (net (code "16") (name "/CH2a_Htr+") (class "Default")
      (node (ref "C3") (pin "1") (pinfunction "1_1") (pintype "passive"))
      (node (ref "D1") (pin "K") (pinfunction "K_K") (pintype "passive"))
      (node (ref "H2a") (pin "1") (pinfunction "TP_1") (pintype "passive"))
      (node (ref "P1") (pin "4") (pinfunction "4_4") (pintype "passive"))
      (node (ref "Q1") (pin "5") (pinfunction "D2_5") (pintype "passive"))
      (node (ref "Q1") (pin "6") (pinfunction "D2_6") (pintype "passive"))
    )
    (net (code "17") (name "/CH2a_Thm+") (class "Default")
      (node (ref "P1") (pin "6") (pinfunction "6_6") (pintype "passive"))
      (node (ref "R22") (pin "2") (pinfunction "2_2") (pintype "passive"))
      (node (ref "R28") (pin "2") (pinfunction "2_2") (pintype "passive"))
    )
    (net (code "18") (name "/CH2b_DRVn") (class "Default")
      (node (ref "D2b") (pin "1") (pinfunction "TP_1") (pintype "passive"))
      (node (ref "Q4") (pin "5") (pinfunction "B2_5") (pintype "passive"))
    )
    (net (code "19") (name "/CH2b_Htr+") (class "Default")
      (node (ref "C4") (pin "1") (pinfunction "1_1") (pintype "passive"))
      (node (ref "D2") (pin "K") (pinfunction "K_K") (pintype "passive"))
      (node (ref "H2b") (pin "1") (pinfunction "TP_1") (pintype "passive"))
      (node (ref "P1") (pin "1") (pinfunction "1_1") (pintype "passive"))
      (node (ref "Q1") (pin "7") (pinfunction "D1_7") (pintype "passive"))
      (node (ref "Q1") (pin "8") (pinfunction "D1_8") (pintype "passive"))
    )
    (net (code "20") (name "/CH2b_Thm+") (class "Default")
      (node (ref "P1") (pin "3") (pinfunction "3_3") (pintype "passive"))
      (node (ref "R24") (pin "2") (pinfunction "2_2") (pintype "passive"))
      (node (ref "R30") (pin "2") (pinfunction "2_2") (pintype "passive"))
    )
    (net (code "21") (name "/COM") (class "Default")
      (node (ref "C11") (pin "1") (pinfunction "1_1") (pintype "passive"))
      (node (ref "C9") (pin "1") (pinfunction "1_1") (pintype "passive"))
      (node (ref "L2") (pin "2") (pinfunction "2_2") (pintype "passive"))
      (node (ref "NT1") (pin "2") (pinfunction "2_2") (pintype "passive"))
      (node (ref "P1") (pin "2") (pinfunction "2_2") (pintype "passive"))
      (node (ref "P2") (pin "2") (pinfunction "2_2") (pintype "passive"))
      (node (ref "Q8") (pin "2") (pinfunction "S_2") (pintype "passive"))
      (node (ref "R11") (pin "2") (pinfunction "2_2") (pintype "passive"))
      (node (ref "R16") (pin "2") (pinfunction "2_2") (pintype "passive"))
      (node (ref "R18") (pin "2") (pinfunction "2_2") (pintype "passive"))
      (node (ref "R29") (pin "1") (pinfunction "1_1") (pintype "passive"))
    )
    (net (code "22") (name "/GAIN") (class "Default")
      (node (ref "R37") (pin "2") (pinfunction "2_2") (pintype "passive"))
    )
    (net (code "23") (name "/HIGH_G_AMP") (class "Default")
      (node (ref "D7") (pin "K") (pinfunction "K_K") (pintype "passive"))
      (node (ref "HGA") (pin "1") (pinfunction "TP_1") (pintype "passive"))
      (node (ref "R17") (pin "1") (pinfunction "1_1") (pintype "passive"))
    )
    (net (code "24") (name "/HIGH_G_IN") (class "Default")
      (node (ref "C35") (pin "2") (pinfunction "2_2") (pintype "passive"))
      (node (ref "R25") (pin "2") (pinfunction "2_2") (pintype "passive"))
      (node (ref "R34") (pin "2") (pinfunction "2_2") (pintype "passive"))
      (node (ref "U2") (pin "1") (pinfunction "A_1") (pintype "passive"))
      (node (ref "U2") (pin "5") (pinfunction "B+_5") (pintype "passive"))
    )
    (net (code "25") (name "/LOW_G_AMP") (class "Default")
      (node (ref "D10") (pin "K") (pinfunction "K_K") (pintype "passive"))
      (node (ref "LGA") (pin "1") (pinfunction "TP_1") (pintype "passive"))
      (node (ref "R25") (pin "1") (pinfunction "1_1") (pintype "passive"))
    )
    (net (code "26") (name "/LOW_G_IN") (class "Default")
      (node (ref "D9") (pin "3") (pinfunction "K_3") (pintype "passive"))
      (node (ref "R21") (pin "1") (pinfunction "1_1") (pintype "passive"))
      (node (ref "U2") (pin "3") (pinfunction "A+_3") (pintype "passive"))
      (node (ref "U3") (pin "13") (pinfunction "1Y1_13") (pintype "passive"))
    )
    (net (code "27") (name "/MUX_En") (class "Default")
      (node (ref "U3") (pin "6") (pinfunction "En_6") (pintype "input"))
    )
    (net (code "28") (name "/MUX_SEL0{slash}ID1") (class "Default")
      (node (ref "R36") (pin "2") (pinfunction "2_2") (pintype "passive"))
      (node (ref "U3") (pin "9") (pinfunction "S0_9") (pintype "input"))
    )
    (net (code "29") (name "/MUX_SEL1{slash}ID2") (class "Default")
      (node (ref "R33") (pin "2") (pinfunction "2_2") (pintype "passive"))
      (node (ref "U3") (pin "10") (pinfunction "S1_10") (pintype "input"))
    )
    (net (code "30") (name "/OVERCURRENT") (class "Default")
      (node (ref "C33") (pin "2") (pinfunction "2_2") (pintype "passive"))
      (node (ref "OC") (pin "1") (pinfunction "TP_1") (pintype "passive"))
      (node (ref "R15") (pin "2") (pinfunction "2_2") (pintype "passive"))
      (node (ref "U1") (pin "4") (pinfunction "Out_4") (pintype "passive"))
    )
    (net (code "31") (name "EARTH") (class "Default")
      (node (ref "ER") (pin "1") (pinfunction "TP_1") (pintype "passive"))
      (node (ref "L2") (pin "1") (pinfunction "1_1") (pintype "passive"))
    )
    (net (code "32") (name "GND") (class "Default")
      (node (ref "C1") (pin "2") (pinfunction "2_2") (pintype "passive"))
      (node (ref "C10") (pin "2") (pinfunction "2_2") (pintype "passive"))
      (node (ref "C11") (pin "2") (pinfunction "2_2") (pintype "passive"))
      (node (ref "C12") (pin "2") (pinfunction "2_2") (pintype "passive"))
      (node (ref "C13") (pin "2") (pinfunction "2_2") (pintype "passive"))
      (node (ref "C14") (pin "2") (pinfunction "2_2") (pintype "passive"))
      (node (ref "C15") (pin "2") (pinfunction "2_2") (pintype "passive"))
      (node (ref "C2") (pin "2") (pinfunction "2_2") (pintype "passive"))
      (node (ref "C3") (pin "2") (pinfunction "2_2") (pintype "passive"))
      (node (ref "C4") (pin "2") (pinfunction "2_2") (pintype "passive"))
      (node (ref "C5") (pin "2") (pinfunction "2_2") (pintype "passive"))
      (node (ref "C6") (pin "2") (pinfunction "2_2") (pintype "passive"))
      (node (ref "C7") (pin "2") (pinfunction "2_2") (pintype "passive"))
      (node (ref "C8") (pin "2") (pinfunction "2_2") (pintype "passive"))
      (node (ref "D1") (pin "A") (pinfunction "A_A") (pintype "passive"))
      (node (ref "D10") (pin "A") (pinfunction "A_A") (pintype "passive"))
      (node (ref "D2") (pin "A") (pinfunction "A_A") (pintype "passive"))
      (node (ref "D3") (pin "A") (pinfunction "A_A") (pintype "passive"))
      (node (ref "D4") (pin "A") (pinfunction "A_A") (pintype "passive"))
      (node (ref "D5") (pin "K") (pinfunction "K_K") (pintype "passive"))
      (node (ref "D6") (pin "K") (pinfunction "K_K") (pintype "passive"))
      (node (ref "D7") (pin "A") (pinfunction "A_A") (pintype "passive"))
      (node (ref "D8") (pin "3") (pinfunction "K_3") (pintype "passive"))
      (node (ref "D9") (pin "1") (pinfunction "A1_1") (pintype "passive"))
      (node (ref "NT1") (pin "1") (pinfunction "1_1") (pintype "passive"))
      (node (ref "U1") (pin "2") (pinfunction "V-_2") (pintype "power_in"))
      (node (ref "U3") (pin "8") (pinfunction "Gnd_8") (pintype "power_in"))
    )
    (net (code "33") (name "Net-(C34-Pad2)") (class "Default")
      (node (ref "C34") (pin "2") (pinfunction "2_2") (pintype "passive"))
      (node (ref "R17") (pin "2") (pinfunction "2_2") (pintype "passive"))
      (node (ref "R19") (pin "2") (pinfunction "2_2") (pintype "passive"))
      (node (ref "U2") (pin "7") (pinfunction "7_7") (pintype "passive"))
      (node (ref "Z5") (pin "K") (pinfunction "K_K") (pintype "passive"))
    )
    (net (code "34") (name "Net-(D5-PadA)") (class "Default")
      (node (ref "D5") (pin "A") (pinfunction "A_A") (pintype "passive"))
      (node (ref "R9") (pin "1") (pinfunction "1_1") (pintype "passive"))
    )
    (net (code "35") (name "Net-(D6-PadA)") (class "Default")
      (node (ref "D6") (pin "A") (pinfunction "A_A") (pintype "passive"))
      (node (ref "R10") (pin "1") (pinfunction "1_1") (pintype "passive"))
    )
    (net (code "36") (name "Net-(D8-A1)") (class "Default")
      (node (ref "C34") (pin "1") (pinfunction "1_1") (pintype "passive"))
      (node (ref "D8") (pin "1") (pinfunction "A1_1") (pintype "passive"))
      (node (ref "D8") (pin "2") (pinfunction "A2_2") (pintype "passive"))
      (node (ref "R18") (pin "1") (pinfunction "1_1") (pintype "passive"))
      (node (ref "R19") (pin "1") (pinfunction "1_1") (pintype "passive"))
      (node (ref "U2") (pin "6") (pinfunction "B-_6") (pintype "passive"))
      (node (ref "Z5") (pin "A") (pinfunction "A_A") (pintype "passive"))
    )
    (net (code "37") (name "Net-(Q1A-G1)") (class "Default")
      (node (ref "Q1") (pin "2") (pinfunction "G1_2") (pintype "passive"))
      (node (ref "R2") (pin "1") (pinfunction "1_1") (pintype "passive"))
      (node (ref "R6") (pin "2") (pinfunction "2_2") (pintype "passive"))
      (node (ref "Z2") (pin "A") (pinfunction "A_A") (pintype "passive"))
    )
    (net (code "38") (name "Net-(Q1B-G2)") (class "Default")
      (node (ref "Q1") (pin "4") (pinfunction "G2_4") (pintype "passive"))
      (node (ref "R1") (pin "1") (pinfunction "1_1") (pintype "passive"))
      (node (ref "R5") (pin "2") (pinfunction "2_2") (pintype "passive"))
      (node (ref "Z1") (pin "A") (pinfunction "A_A") (pintype "passive"))
    )
    (net (code "39") (name "Net-(Q2A-G1)") (class "Default")
      (node (ref "Q2") (pin "2") (pinfunction "G1_2") (pintype "passive"))
      (node (ref "R4") (pin "1") (pinfunction "1_1") (pintype "passive"))
      (node (ref "R8") (pin "2") (pinfunction "2_2") (pintype "passive"))
      (node (ref "Z4") (pin "A") (pinfunction "A_A") (pintype "passive"))
    )
    (net (code "40") (name "Net-(Q2B-G2)") (class "Default")
      (node (ref "Q2") (pin "4") (pinfunction "G2_4") (pintype "passive"))
      (node (ref "R3") (pin "1") (pinfunction "1_1") (pintype "passive"))
      (node (ref "R7") (pin "2") (pinfunction "2_2") (pintype "passive"))
      (node (ref "Z3") (pin "A") (pinfunction "A_A") (pintype "passive"))
    )
    (net (code "41") (name "Net-(Q3-C1)") (class "Default")
      (node (ref "Q3") (pin "6") (pinfunction "C1_6") (pintype "passive"))
      (node (ref "R5") (pin "1") (pinfunction "1_1") (pintype "passive"))
    )
    (net (code "42") (name "Net-(Q4-B1)") (class "Default")
      (node (ref "Q4") (pin "2") (pinfunction "B1_2") (pintype "passive"))
      (node (ref "Q4") (pin "3") (pinfunction "C2_3") (pintype "passive"))
    )
    (net (code "43") (name "Net-(Q4-C1)") (class "Default")
      (node (ref "Q4") (pin "6") (pinfunction "C1_6") (pintype "passive"))
      (node (ref "R6") (pin "1") (pinfunction "1_1") (pintype "passive"))
    )
    (net (code "44") (name "Net-(Q5-C1)") (class "Default")
      (node (ref "Q5") (pin "6") (pinfunction "C1_6") (pintype "passive"))
      (node (ref "R7") (pin "1") (pinfunction "1_1") (pintype "passive"))
    )
    (net (code "45") (name "Net-(Q6-B1)") (class "Default")
      (node (ref "Q6") (pin "2") (pinfunction "B1_2") (pintype "passive"))
      (node (ref "Q6") (pin "3") (pinfunction "C2_3") (pintype "passive"))
    )
    (net (code "46") (name "Net-(Q6-C1)") (class "Default")
      (node (ref "Q6") (pin "6") (pinfunction "C1_6") (pintype "passive"))
      (node (ref "R8") (pin "1") (pinfunction "1_1") (pintype "passive"))
    )
    (net (code "47") (name "Net-(Q7-D)") (class "Default")
      (node (ref "Q7") (pin "3") (pinfunction "D_3") (pintype "passive"))
      (node (ref "R23") (pin "1") (pinfunction "1_1") (pintype "passive"))
    )
    (net (code "48") (name "Net-(Q7-G)") (class "Default")
      (node (ref "Q7") (pin "1") (pinfunction "G_1") (pintype "passive"))
      (node (ref "R20") (pin "2") (pinfunction "2_2") (pintype "passive"))
    )
    (net (code "49") (name "Net-(Q8-D)") (class "Default")
      (node (ref "Q8") (pin "3") (pinfunction "D_3") (pintype "passive"))
      (node (ref "R35") (pin "2") (pinfunction "2_2") (pintype "passive"))
    )
    (net (code "50") (name "Net-(Q8-G)") (class "Default")
      (node (ref "Q8") (pin "1") (pinfunction "G_1") (pintype "passive"))
      (node (ref "R37") (pin "1") (pinfunction "1_1") (pintype "passive"))
    )
    (net (code "51") (name "Net-(R32-Pad1)") (class "Default")
      (node (ref "R32") (pin "1") (pinfunction "1_1") (pintype "passive"))
      (node (ref "U3") (pin "11") (pinfunction "S1_11") (pintype "passive"))
    )
    (net (code "52") (name "Net-(U1A-In+)") (class "Default")
      (node (ref "R11") (pin "1") (pinfunction "1_1") (pintype "passive"))
      (node (ref "U1") (pin "1") (pinfunction "In+_1") (pintype "passive"))
    )
    (net (code "53") (name "Net-(U1A-In-)") (class "Default")
      (node (ref "C33") (pin "1") (pinfunction "1_1") (pintype "passive"))
      (node (ref "R14") (pin "1") (pinfunction "1_1") (pintype "passive"))
      (node (ref "R15") (pin "1") (pinfunction "1_1") (pintype "passive"))
      (node (ref "U1") (pin "3") (pinfunction "In-_3") (pintype "passive"))
    )
    (net (code "54") (name "Net-(U2A-A-)") (class "Default")
      (node (ref "C35") (pin "1") (pinfunction "1_1") (pintype "passive"))
      (node (ref "R29") (pin "2") (pinfunction "2_2") (pintype "passive"))
      (node (ref "R34") (pin "1") (pinfunction "1_1") (pintype "passive"))
      (node (ref "R35") (pin "1") (pinfunction "1_1") (pintype "passive"))
      (node (ref "U2") (pin "2") (pinfunction "A-_2") (pintype "passive"))
    )
    (net (code "55") (name "Net-(U3-1Y0)") (class "Default")
      (node (ref "R28") (pin "1") (pinfunction "1_1") (pintype "passive"))
      (node (ref "U3") (pin "12") (pinfunction "1Y0_12") (pintype "passive"))
    )
    (net (code "56") (name "Net-(U3-1Z)") (class "Default")
      (node (ref "R31") (pin "1") (pinfunction "1_1") (pintype "passive"))
      (node (ref "U3") (pin "14") (pinfunction "1Z_14") (pintype "passive"))
    )
    (net (code "57") (name "Net-(U3-2Y0)") (class "Default")
      (node (ref "R24") (pin "1") (pinfunction "1_1") (pintype "passive"))
      (node (ref "U3") (pin "2") (pinfunction "2Y0_2") (pintype "passive"))
    )
    (net (code "58") (name "Net-(U3-2Y1)") (class "Default")
      (node (ref "R22") (pin "1") (pinfunction "1_1") (pintype "passive"))
      (node (ref "U3") (pin "1") (pinfunction "2Y1_1") (pintype "passive"))
    )
    (net (code "59") (name "Net-(U3-2Z)") (class "Default")
      (node (ref "R30") (pin "1") (pinfunction "1_1") (pintype "passive"))
      (node (ref "U3") (pin "15") (pinfunction "2Z_15") (pintype "passive"))
    )
    (net (code "60") (name "Net-(U3-3Y0)") (class "Default")
      (node (ref "R26") (pin "1") (pinfunction "1_1") (pintype "passive"))
      (node (ref "U3") (pin "5") (pinfunction "3Y0_5") (pintype "passive"))
    )
    (net (code "61") (name "Net-(U3-3Y1)") (class "Default")
      (node (ref "R23") (pin "2") (pinfunction "2_2") (pintype "passive"))
      (node (ref "U3") (pin "3") (pinfunction "3Y1_3") (pintype "passive"))
    )
    (net (code "62") (name "Net-(U3-3Z)") (class "Default")
      (node (ref "R27") (pin "1") (pinfunction "1_1") (pintype "passive"))
      (node (ref "U3") (pin "4") (pinfunction "3Z_4") (pintype "passive"))
    )
    (net (code "63") (name "Vnn") (class "Default")
      (node (ref "C9") (pin "2") (pinfunction "2_2") (pintype "passive"))
      (node (ref "R14") (pin "2") (pinfunction "2_2") (pintype "passive"))
      (node (ref "R16") (pin "1") (pinfunction "1_1") (pintype "passive"))
    )
    (net (code "64") (name "Vpp") (class "Default")
      (node (ref "Q1") (pin "1") (pinfunction "S1_1") (pintype "passive"))
      (node (ref "Q1") (pin "3") (pinfunction "S2_3") (pintype "passive"))
      (node (ref "Q2") (pin "1") (pinfunction "S1_1") (pintype "passive"))
      (node (ref "Q2") (pin "3") (pinfunction "S2_3") (pintype "passive"))
      (node (ref "R1") (pin "2") (pinfunction "2_2") (pintype "passive"))
      (node (ref "R2") (pin "2") (pinfunction "2_2") (pintype "passive"))
      (node (ref "R3") (pin "2") (pinfunction "2_2") (pintype "passive"))
      (node (ref "R4") (pin "2") (pinfunction "2_2") (pintype "passive"))
      (node (ref "Z1") (pin "K") (pinfunction "K_K") (pintype "passive"))
      (node (ref "Z2") (pin "K") (pinfunction "K_K") (pintype "passive"))
      (node (ref "Z3") (pin "K") (pinfunction "K_K") (pintype "passive"))
      (node (ref "Z4") (pin "K") (pinfunction "K_K") (pintype "passive"))
    )
    (net (code "65") (name "unconnected-(Z5-PadNC)") (class "Default")
      (node (ref "Z5") (pin "NC") (pinfunction "NC_NC") (pintype "passive"))
    )
  )
)
